# BOARD_GPIO.net
KiCad netlist of a schematic drawn in Altium Designer
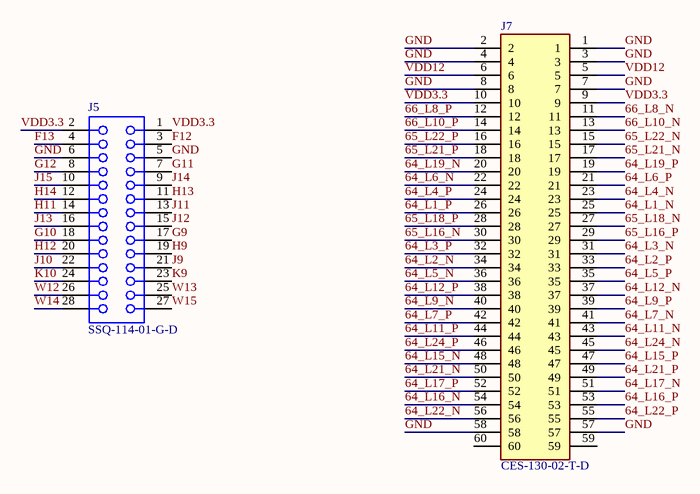
[diagram p0: BOARD_GPIO.SchDoc]

(export (version "E")
  (design (tool "Eeschema 10.0.6"))
  (components
    (comp (ref "J5")
      (value "SSQ-114-01-G-D")
      (footprint "SMTC-SSQ-114-01-X-D")
      (description "SQ Post Socket, Through-hole, Vertical, -55 to 125 degC, 2.54 mm Pitch, 28-Pin, Female, RoHS")
      (fields (field (name "MANUFACTURER") "Samtec"))
      (libsource (lib "Altium Content Vault") (part "SMTC-SSQ-114-01-X-D"))
    )
    (comp (ref "J7")
      (value "CES-130-02-T-D")
      (footprint "SamacSys:CES-130-XX-X-D")
      (description "Connector")
      (libsource (lib "*") (part "CES-130-02-T-D"))
    )
  )
  (nets
    (net (code "1") (name "/64_L1_N") (class "Default")
      (node (ref "J7") (pin "25") (pinfunction "25_25") (pintype "passive"))
    )
    (net (code "2") (name "/64_L1_P") (class "Default")
      (node (ref "J7") (pin "26") (pinfunction "26_26") (pintype "passive"))
    )
    (net (code "3") (name "/64_L2_N") (class "Default")
      (node (ref "J7") (pin "34") (pinfunction "34_34") (pintype "passive"))
    )
    (net (code "4") (name "/64_L2_P") (class "Default")
      (node (ref "J7") (pin "33") (pinfunction "33_33") (pintype "passive"))
    )
    (net (code "5") (name "/64_L3_N") (class "Default")
      (node (ref "J7") (pin "31") (pinfunction "31_31") (pintype "passive"))
    )
    (net (code "6") (name "/64_L3_P") (class "Default")
      (node (ref "J7") (pin "32") (pinfunction "32_32") (pintype "passive"))
    )
    (net (code "7") (name "/64_L4_N") (class "Default")
      (node (ref "J7") (pin "23") (pinfunction "23_23") (pintype "passive"))
    )
    (net (code "8") (name "/64_L4_P") (class "Default")
      (node (ref "J7") (pin "24") (pinfunction "24_24") (pintype "passive"))
    )
    (net (code "9") (name "/64_L5_N") (class "Default")
      (node (ref "J7") (pin "36") (pinfunction "36_36") (pintype "passive"))
    )
    (net (code "10") (name "/64_L5_P") (class "Default")
      (node (ref "J7") (pin "35") (pinfunction "35_35") (pintype "passive"))
    )
    (net (code "11") (name "/64_L6_N") (class "Default")
      (node (ref "J7") (pin "22") (pinfunction "22_22") (pintype "passive"))
    )
    (net (code "12") (name "/64_L6_P") (class "Default")
      (node (ref "J7") (pin "21") (pinfunction "21_21") (pintype "passive"))
    )
    (net (code "13") (name "/64_L7_N") (class "Default")
      (node (ref "J7") (pin "41") (pinfunction "41_41") (pintype "passive"))
    )
    (net (code "14") (name "/64_L7_P") (class "Default")
      (node (ref "J7") (pin "42") (pinfunction "42_42") (pintype "passive"))
    )
    (net (code "15") (name "/64_L9_N") (class "Default")
      (node (ref "J7") (pin "40") (pinfunction "40_40") (pintype "passive"))
    )
    (net (code "16") (name "/64_L9_P") (class "Default")
      (node (ref "J7") (pin "39") (pinfunction "39_39") (pintype "passive"))
    )
    (net (code "17") (name "/64_L11_N") (class "Default")
      (node (ref "J7") (pin "43") (pinfunction "43_43") (pintype "passive"))
    )
    (net (code "18") (name "/64_L11_P") (class "Default")
      (node (ref "J7") (pin "44") (pinfunction "44_44") (pintype "passive"))
    )
    (net (code "19") (name "/64_L12_N") (class "Default")
      (node (ref "J7") (pin "37") (pinfunction "37_37") (pintype "passive"))
    )
    (net (code "20") (name "/64_L12_P") (class "Default")
      (node (ref "J7") (pin "38") (pinfunction "38_38") (pintype "passive"))
    )
    (net (code "21") (name "/64_L15_N") (class "Default")
      (node (ref "J7") (pin "48") (pinfunction "48_48") (pintype "passive"))
    )
    (net (code "22") (name "/64_L15_P") (class "Default")
      (node (ref "J7") (pin "47") (pinfunction "47_47") (pintype "passive"))
    )
    (net (code "23") (name "/64_L16_N") (class "Default")
      (node (ref "J7") (pin "54") (pinfunction "54_54") (pintype "passive"))
    )
    (net (code "24") (name "/64_L16_P") (class "Default")
      (node (ref "J7") (pin "53") (pinfunction "53_53") (pintype "passive"))
    )
    (net (code "25") (name "/64_L17_N") (class "Default")
      (node (ref "J7") (pin "51") (pinfunction "51_51") (pintype "passive"))
    )
    (net (code "26") (name "/64_L17_P") (class "Default")
      (node (ref "J7") (pin "52") (pinfunction "52_52") (pintype "passive"))
    )
    (net (code "27") (name "/64_L19_N") (class "Default")
      (node (ref "J7") (pin "20") (pinfunction "20_20") (pintype "passive"))
    )
    (net (code "28") (name "/64_L19_P") (class "Default")
      (node (ref "J7") (pin "19") (pinfunction "19_19") (pintype "passive"))
    )
    (net (code "29") (name "/64_L21_N") (class "Default")
      (node (ref "J7") (pin "50") (pinfunction "50_50") (pintype "passive"))
    )
    (net (code "30") (name "/64_L21_P") (class "Default")
      (node (ref "J7") (pin "49") (pinfunction "49_49") (pintype "passive"))
    )
    (net (code "31") (name "/64_L22_N") (class "Default")
      (node (ref "J7") (pin "56") (pinfunction "56_56") (pintype "passive"))
    )
    (net (code "32") (name "/64_L22_P") (class "Default")
      (node (ref "J7") (pin "55") (pinfunction "55_55") (pintype "passive"))
    )
    (net (code "33") (name "/64_L24_N") (class "Default")
      (node (ref "J7") (pin "45") (pinfunction "45_45") (pintype "passive"))
    )
    (net (code "34") (name "/64_L24_P") (class "Default")
      (node (ref "J7") (pin "46") (pinfunction "46_46") (pintype "passive"))
    )
    (net (code "35") (name "/65_L16_N") (class "Default")
      (node (ref "J7") (pin "30") (pinfunction "30_30") (pintype "passive"))
    )
    (net (code "36") (name "/65_L16_P") (class "Default")
      (node (ref "J7") (pin "29") (pinfunction "29_29") (pintype "passive"))
    )
    (net (code "37") (name "/65_L18_N") (class "Default")
      (node (ref "J7") (pin "27") (pinfunction "27_27") (pintype "passive"))
    )
    (net (code "38") (name "/65_L18_P") (class "Default")
      (node (ref "J7") (pin "28") (pinfunction "28_28") (pintype "passive"))
    )
    (net (code "39") (name "/65_L21_N") (class "Default")
      (node (ref "J7") (pin "17") (pinfunction "17_17") (pintype "passive"))
    )
    (net (code "40") (name "/65_L21_P") (class "Default")
      (node (ref "J7") (pin "18") (pinfunction "18_18") (pintype "passive"))
    )
    (net (code "41") (name "/65_L22_N") (class "Default")
      (node (ref "J7") (pin "15") (pinfunction "15_15") (pintype "passive"))
    )
    (net (code "42") (name "/65_L22_P") (class "Default")
      (node (ref "J7") (pin "16") (pinfunction "16_16") (pintype "passive"))
    )
    (net (code "43") (name "/66_L8_N") (class "Default")
      (node (ref "J7") (pin "11") (pinfunction "11_11") (pintype "passive"))
    )
    (net (code "44") (name "/66_L8_P") (class "Default")
      (node (ref "J7") (pin "12") (pinfunction "12_12") (pintype "passive"))
    )
    (net (code "45") (name "/66_L10_N") (class "Default")
      (node (ref "J7") (pin "13") (pinfunction "13_13") (pintype "passive"))
    )
    (net (code "46") (name "/66_L10_P") (class "Default")
      (node (ref "J7") (pin "14") (pinfunction "14_14") (pintype "passive"))
    )
    (net (code "47") (name "/F12") (class "Default")
      (node (ref "J5") (pin "3") (pinfunction "3_3") (pintype "passive"))
    )
    (net (code "48") (name "/F13") (class "Default")
      (node (ref "J5") (pin "4") (pinfunction "4_4") (pintype "passive"))
    )
    (net (code "49") (name "/G9") (class "Default")
      (node (ref "J5") (pin "17") (pinfunction "17_17") (pintype "passive"))
    )
    (net (code "50") (name "/G10") (class "Default")
      (node (ref "J5") (pin "18") (pinfunction "18_18") (pintype "passive"))
    )
    (net (code "51") (name "/G11") (class "Default")
      (node (ref "J5") (pin "7") (pinfunction "7_7") (pintype "passive"))
    )
    (net (code "52") (name "/G12") (class "Default")
      (node (ref "J5") (pin "8") (pinfunction "8_8") (pintype "passive"))
    )
    (net (code "53") (name "/GND") (class "Default")
      (node (ref "J5") (pin "5") (pinfunction "5_5") (pintype "passive"))
      (node (ref "J5") (pin "6") (pinfunction "6_6") (pintype "passive"))
      (node (ref "J7") (pin "1") (pinfunction "1_1") (pintype "passive"))
      (node (ref "J7") (pin "2") (pinfunction "2_2") (pintype "passive"))
      (node (ref "J7") (pin "3") (pinfunction "3_3") (pintype "passive"))
      (node (ref "J7") (pin "4") (pinfunction "4_4") (pintype "passive"))
      (node (ref "J7") (pin "57") (pinfunction "57_57") (pintype "passive"))
      (node (ref "J7") (pin "58") (pinfunction "58_58") (pintype "passive"))
      (node (ref "J7") (pin "7") (pinfunction "7_7") (pintype "passive"))
      (node (ref "J7") (pin "8") (pinfunction "8_8") (pintype "passive"))
    )
    (net (code "54") (name "/H9") (class "Default")
      (node (ref "J5") (pin "19") (pinfunction "19_19") (pintype "passive"))
    )
    (net (code "55") (name "/H11") (class "Default")
      (node (ref "J5") (pin "14") (pinfunction "14_14") (pintype "passive"))
    )
    (net (code "56") (name "/H12") (class "Default")
      (node (ref "J5") (pin "20") (pinfunction "20_20") (pintype "passive"))
    )
    (net (code "57") (name "/H13") (class "Default")
      (node (ref "J5") (pin "11") (pinfunction "11_11") (pintype "passive"))
    )
    (net (code "58") (name "/H14") (class "Default")
      (node (ref "J5") (pin "12") (pinfunction "12_12") (pintype "passive"))
    )
    (net (code "59") (name "/J9") (class "Default")
      (node (ref "J5") (pin "21") (pinfunction "21_21") (pintype "passive"))
    )
    (net (code "60") (name "/J10") (class "Default")
      (node (ref "J5") (pin "22") (pinfunction "22_22") (pintype "passive"))
    )
    (net (code "61") (name "/J11") (class "Default")
      (node (ref "J5") (pin "13") (pinfunction "13_13") (pintype "passive"))
    )
    (net (code "62") (name "/J12") (class "Default")
      (node (ref "J5") (pin "15") (pinfunction "15_15") (pintype "passive"))
    )
    (net (code "63") (name "/J13") (class "Default")
      (node (ref "J5") (pin "16") (pinfunction "16_16") (pintype "passive"))
    )
    (net (code "64") (name "/J14") (class "Default")
      (node (ref "J5") (pin "9") (pinfunction "9_9") (pintype "passive"))
    )
    (net (code "65") (name "/J15") (class "Default")
      (node (ref "J5") (pin "10") (pinfunction "10_10") (pintype "passive"))
    )
    (net (code "66") (name "/K9") (class "Default")
      (node (ref "J5") (pin "23") (pinfunction "23_23") (pintype "passive"))
    )
    (net (code "67") (name "/K10") (class "Default")
      (node (ref "J5") (pin "24") (pinfunction "24_24") (pintype "passive"))
    )
    (net (code "68") (name "/VDD3.3") (class "Default")
      (node (ref "J5") (pin "1") (pinfunction "1_1") (pintype "passive"))
      (node (ref "J5") (pin "2") (pinfunction "2_2") (pintype "passive"))
      (node (ref "J7") (pin "10") (pinfunction "10_10") (pintype "passive"))
      (node (ref "J7") (pin "9") (pinfunction "9_9") (pintype "passive"))
    )
    (net (code "69") (name "/VDD12") (class "Default")
      (node (ref "J7") (pin "5") (pinfunction "5_5") (pintype "passive"))
      (node (ref "J7") (pin "6") (pinfunction "6_6") (pintype "passive"))
    )
    (net (code "70") (name "/W12") (class "Default")
      (node (ref "J5") (pin "26") (pinfunction "26_26") (pintype "passive"))
    )
    (net (code "71") (name "/W13") (class "Default")
      (node (ref "J5") (pin "25") (pinfunction "25_25") (pintype "passive"))
    )
    (net (code "72") (name "/W14") (class "Default")
      (node (ref "J5") (pin "28") (pinfunction "28_28") (pintype "passive"))
    )
    (net (code "73") (name "/W15") (class "Default")
      (node (ref "J5") (pin "27") (pinfunction "27_27") (pintype "passive"))
    )
    (net (code "74") (name "unconnected-(J7-Pad59)") (class "Default")
      (node (ref "J7") (pin "59") (pinfunction "59_59") (pintype "passive"))
    )
    (net (code "75") (name "unconnected-(J7-Pad60)") (class "Default")
      (node (ref "J7") (pin "60") (pinfunction "60_60") (pintype "passive"))
    )
  )
)
